# Adaptator.net
KiCad netlist of a schematic drawn in Altium Designer
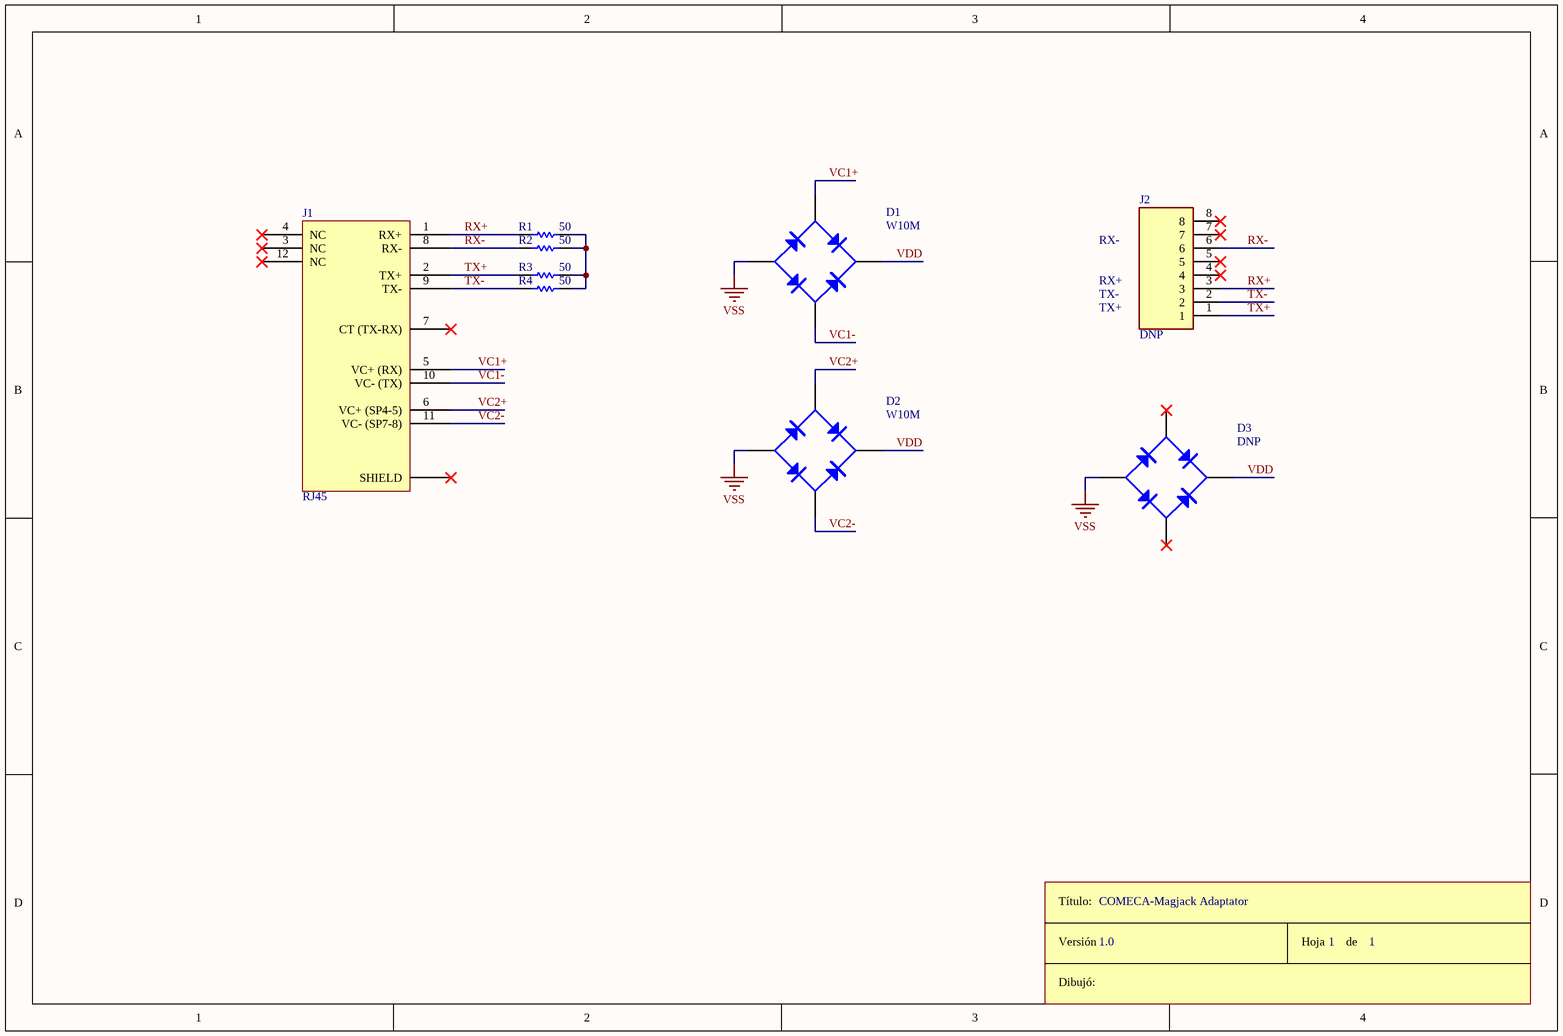
[diagram p0: Adaptator.SchDoc]

(export (version "E")
  (design (tool "Eeschema 10.0.6"))
  (components
    (comp (ref "D1") (value "W10M") (footprint "PUENTE - W10M") (libsource (lib "LIBEBAL") (part "PUENTE")))
    (comp (ref "D2") (value "W10M") (footprint "PUENTE - W10M") (libsource (lib "LIBEBAL") (part "PUENTE")))
    (comp (ref "D3") (value "DNP") (footprint "PUENTE - W10M") (libsource (lib "LIBEBAL") (part "PUENTE")))
    (comp (ref "J1")
      (value "RJ45")
      (footprint "ARJP11C-MB")
      (description "Magjack Connector for PoE")
      (libsource (lib "AditionalComponents") (part "ARJP11C-MBSC-L2"))
    )
    (comp (ref "J2")
      (value "DNP")
      (footprint "CUI_CRJ032-1-TH")
      (description "8P8C, Single Port, Horizontal, Unshielded, No LED, Through Hole, RJ45 Modular Connector")
      (fields (field (name "MP") "CRJ032-1-TH") (field (name "MF") "CUI Devices"))
      (libsource (lib "CRJ032-1-TH") (part "CRJ032-1-TH"))
    )
    (comp (ref "R1") (value "50") (footprint "RES400") (libsource (lib "LIBEBAL") (part "RES")))
    (comp (ref "R2") (value "50") (footprint "RES400") (libsource (lib "LIBEBAL") (part "RES")))
    (comp (ref "R3") (value "50") (footprint "RES400") (libsource (lib "LIBEBAL") (part "RES")))
    (comp (ref "R4") (value "50") (footprint "RES400") (libsource (lib "LIBEBAL") (part "RES")))
    (comp (ref "ROT1") (value "Rotulo") (libsource (lib "LIB PIO IX") (part "Rótulo")))
  )
  (nets
    (net (code "1") (name "/RX+") (class "Default")
      (node (ref "J1") (pin "1") (pinfunction "RX+_1") (pintype "passive"))
      (node (ref "J2") (pin "3") (pinfunction "3_3") (pintype "passive"))
      (node (ref "R1") (pin "1") (pinfunction "1_1") (pintype "passive"))
    )
    (net (code "2") (name "/RX-") (class "Default")
      (node (ref "J1") (pin "8") (pinfunction "RX-_8") (pintype "passive"))
      (node (ref "J2") (pin "6") (pinfunction "6_6") (pintype "passive"))
      (node (ref "R2") (pin "1") (pinfunction "1_1") (pintype "passive"))
    )
    (net (code "3") (name "/TX+") (class "Default")
      (node (ref "J1") (pin "2") (pinfunction "TX+_2") (pintype "passive"))
      (node (ref "J2") (pin "1") (pinfunction "1_1") (pintype "passive"))
      (node (ref "R3") (pin "1") (pinfunction "1_1") (pintype "passive"))
    )
    (net (code "4") (name "/TX-") (class "Default")
      (node (ref "J1") (pin "9") (pinfunction "TX-_9") (pintype "passive"))
      (node (ref "J2") (pin "2") (pinfunction "2_2") (pintype "passive"))
      (node (ref "R4") (pin "1") (pinfunction "1_1") (pintype "passive"))
    )
    (net (code "5") (name "/VC1+") (class "Default")
      (node (ref "D1") (pin "2") (pinfunction "AC_2") (pintype "passive"))
      (node (ref "J1") (pin "5") (pinfunction "VC+_(RX)_5") (pintype "passive"))
    )
    (net (code "6") (name "/VC1-") (class "Default")
      (node (ref "D1") (pin "4") (pinfunction "AC_4") (pintype "passive"))
      (node (ref "J1") (pin "10") (pinfunction "VC-_(TX)_10") (pintype "passive"))
    )
    (net (code "7") (name "/VC2+") (class "Default")
      (node (ref "D2") (pin "2") (pinfunction "AC_2") (pintype "passive"))
      (node (ref "J1") (pin "6") (pinfunction "VC+_(SP4-5)_6") (pintype "passive"))
    )
    (net (code "8") (name "/VC2-") (class "Default")
      (node (ref "D2") (pin "4") (pinfunction "AC_4") (pintype "passive"))
      (node (ref "J1") (pin "11") (pinfunction "VC-_(SP7-8)_11") (pintype "passive"))
    )
    (net (code "9") (name "/VDD") (class "Default")
      (node (ref "D1") (pin "1") (pinfunction "V+_1") (pintype "passive"))
      (node (ref "D2") (pin "1") (pinfunction "V+_1") (pintype "passive"))
      (node (ref "D3") (pin "1") (pinfunction "V+_1") (pintype "passive"))
    )
    (net (code "10") (name "Net-(R1-Pad2)") (class "Default")
      (node (ref "R1") (pin "2") (pinfunction "2_2") (pintype "passive"))
      (node (ref "R2") (pin "2") (pinfunction "2_2") (pintype "passive"))
      (node (ref "R3") (pin "2") (pinfunction "2_2") (pintype "passive"))
      (node (ref "R4") (pin "2") (pinfunction "2_2") (pintype "passive"))
    )
    (net (code "11") (name "VSS") (class "Default")
      (node (ref "D1") (pin "3") (pinfunction "V-_3") (pintype "passive"))
      (node (ref "D2") (pin "3") (pinfunction "V-_3") (pintype "passive"))
      (node (ref "D3") (pin "3") (pinfunction "V-_3") (pintype "passive"))
    )
    (net (code "12") (name "unconnected-(D3-AC-Pad2)") (class "Default")
      (node (ref "D3") (pin "2") (pinfunction "AC_2") (pintype "passive+no_connect"))
    )
    (net (code "13") (name "unconnected-(D3-AC-Pad4)") (class "Default")
      (node (ref "D3") (pin "4") (pinfunction "AC_4") (pintype "passive+no_connect"))
    )
    (net (code "14") (name "unconnected-(J1-CT_(TX-RX)-Pad7)") (class "Default")
      (node (ref "J1") (pin "7") (pinfunction "CT_(TX-RX)_7") (pintype "passive+no_connect"))
    )
    (net (code "15") (name "unconnected-(J1-NC-Pad3)") (class "Default")
      (node (ref "J1") (pin "3") (pinfunction "NC_3") (pintype "passive+no_connect"))
    )
    (net (code "16") (name "unconnected-(J1-NC-Pad4)") (class "Default")
      (node (ref "J1") (pin "4") (pinfunction "NC_4") (pintype "passive+no_connect"))
    )
    (net (code "17") (name "unconnected-(J1-NC-Pad12)") (class "Default")
      (node (ref "J1") (pin "12") (pinfunction "NC_12") (pintype "passive+no_connect"))
    )
    (net (code "18") (name "unconnected-(J1-PadSHIELD)") (class "Default")
      (node (ref "J1") (pin "SHIELD") (pinfunction "SHIELD_SHIELD") (pintype "passive+no_connect"))
    )
    (net (code "19") (name "unconnected-(J2-Pad4)") (class "Default")
      (node (ref "J2") (pin "4") (pinfunction "4_4") (pintype "passive+no_connect"))
    )
    (net (code "20") (name "unconnected-(J2-Pad5)") (class "Default")
      (node (ref "J2") (pin "5") (pinfunction "5_5") (pintype "passive+no_connect"))
    )
    (net (code "21") (name "unconnected-(J2-Pad7)") (class "Default")
      (node (ref "J2") (pin "7") (pinfunction "7_7") (pintype "passive+no_connect"))
    )
    (net (code "22") (name "unconnected-(J2-Pad8)") (class "Default")
      (node (ref "J2") (pin "8") (pinfunction "8_8") (pintype "passive+no_connect"))
    )
  )
)
